# 12_Supply.net
KiCad netlist of a schematic drawn in Altium Designer
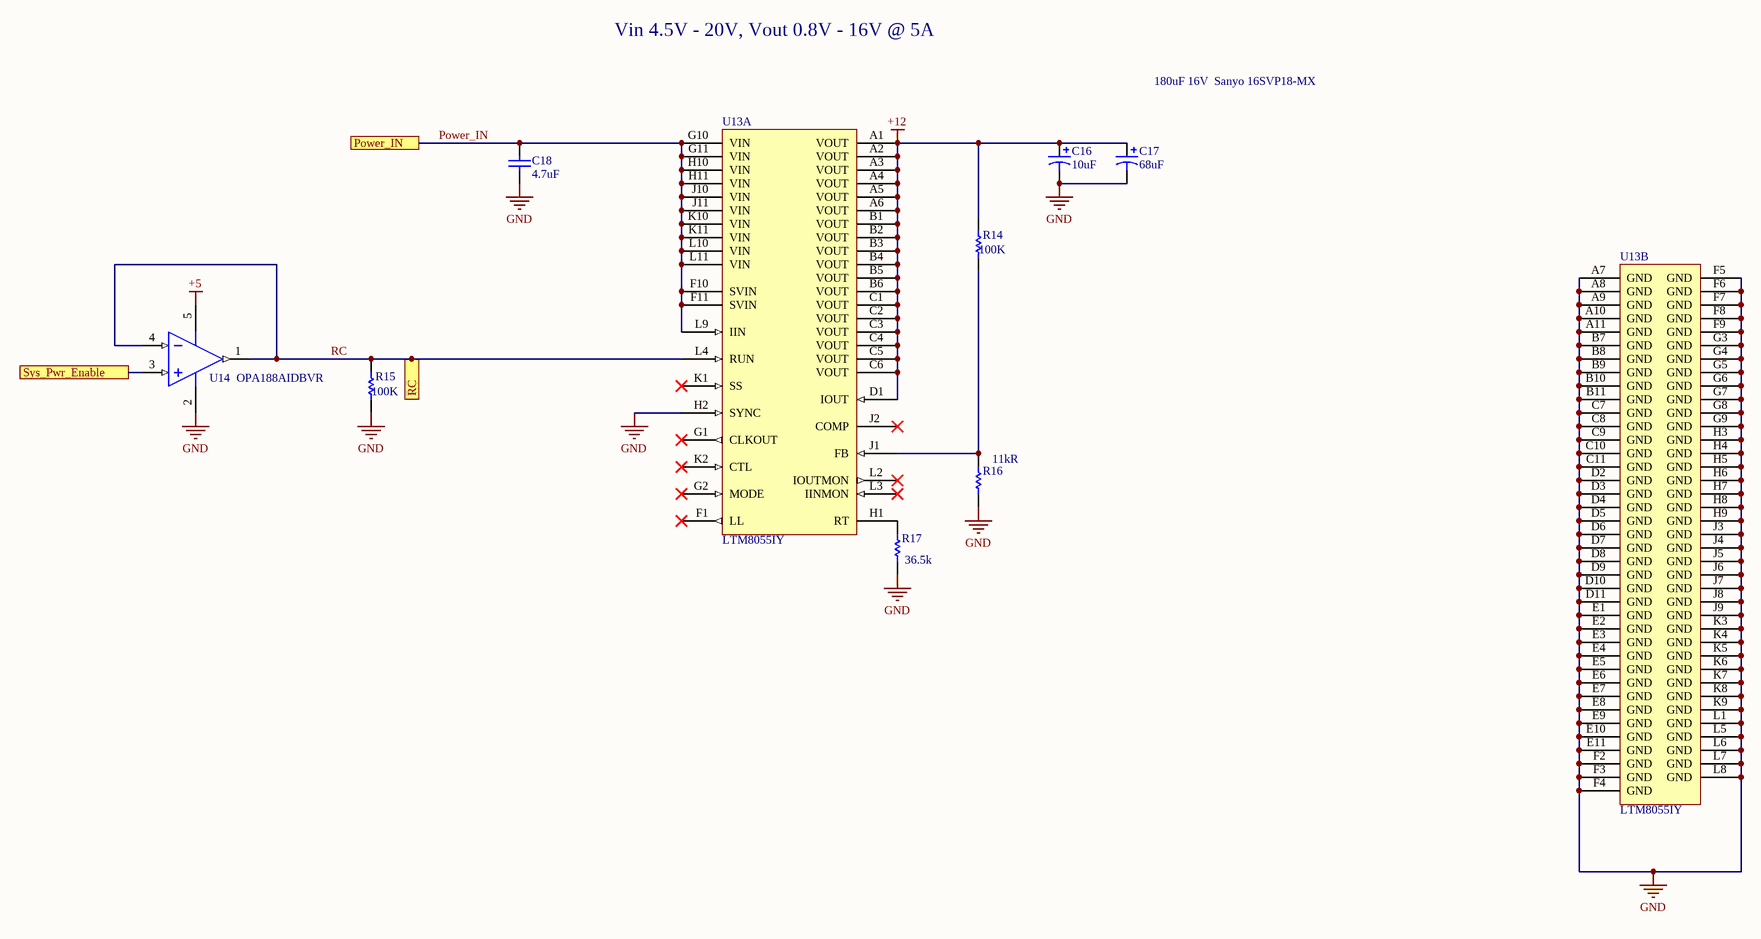
[diagram p0: 12_Supply.SchDoc]

(export (version "E")
  (design (tool "Eeschema 10.0.6"))
  (components
    (comp (ref "C16")
      (value "10uF")
      (footprint "C0805")
      (description "Polarized Capacitor (Surface Mount)")
      (libsource (lib "Miscellaneous Devices") (part "Cap Pol3"))
    )
    (comp (ref "C17")
      (value "68uF")
      (footprint "AVX-CAPC7343_V")
      (description "CAP TANT POLY 68UF 25V 2917")
      (fields
        (field (name "MANUFACTURER") "Kyocera AVX")
        (field (name "MANUFACTURER PART NUMBER") "TCJE686M025R0050")
      )
      (libsource (lib "Altium Content Vault") (part "AVX-CAP-P-2"))
    )
    (comp (ref "C18")
      (value "4.7uF")
      (footprint "CAPC1210(3225)100_M")
      (description "CAP CER 4.7UF 50V X7R 1210")
      (fields
        (field (name "MANUFACTURER") "Murata")
        (field (name "MANUFACTURER PART NUMBER") "GCM32ER71H475KA55K")
      )
      (libsource (lib "Altium Content Vault") (part "CAP"))
    )
    (comp (ref "R14")
      (value "RES SMD 100K OHM 1% 1/8W 0805")
      (footprint "RESC0805(2012)_M")
      (fields
        (field (name "MANUFACTURER") "Vishay")
        (field (name "MANUFACTURER PART NUMBER") "CRCW0805100KFKEA")
        (field (name "TOLERANCE") "1%")
        (field (name "RESISTANCE") "100K")
      )
      (libsource (lib "Altium Content Vault") (part "CMP-1013-00017-1"))
    )
    (comp (ref "R15")
      (value "RES SMD 100K OHM 1% 1/8W 0805")
      (footprint "RESC0805(2012)_M")
      (fields
        (field (name "MANUFACTURER") "Vishay")
        (field (name "MANUFACTURER PART NUMBER") "CRCW0805100KFKEA")
        (field (name "TOLERANCE") "1%")
        (field (name "RESISTANCE") "100K")
      )
      (libsource (lib "Altium Content Vault") (part "CMP-1013-00017-1"))
    )
    (comp (ref "R16")
      (value "RES SMD 11K OHM 1% 1/8W 0805")
      (footprint "RESC0805(2012)_M")
      (fields
        (field (name "MANUFACTURER") "TE Connectivity Holsworthy")
        (field (name "MANUFACTURER PART NUMBER") "CRG0805F11K")
        (field (name "RESISTANCE") "11kR")
        (field (name "TOLERANCE") "1%")
      )
      (libsource (lib "Altium Content Vault") (part "CMP-1013-00017-1"))
    )
    (comp (ref "R17")
      (value "RES SMD 35K OHM 1% 1/8W 0805")
      (footprint "RESC0805(2012)_M")
      (fields
        (field (name "MANUFACTURER") "Vishay")
        (field (name "MANUFACTURER PART NUMBER") "CRCW080536K5FKEA")
        (field (name "TOLERANCE") "1%")
        (field (name "RESISTANCE") "36.5k")
      )
      (libsource (lib "Altium Content Vault") (part "CMP-1013-00017-1"))
    )
    (comp (ref "U13")
      (value "LTM8055IY")
      (footprint "LT-BGA-121-15000X15000X4920")
      (description "Buck-Boost uModule Regulator, 8.5 A, 5 to 36 V, -40 to 125 degC, 121-Ball BGA, RoHS, Tray")
      (fields (field (name "MANUFACTURER") "LinearTechnology"))
      (libsource (lib "Altium Content Vault") (part "LT-LTM8055-BGA-121"))
    )
    (comp (ref "U14")
      (value "OPA188AIDBVR")
      (footprint "DBV0005A_M")
      (fields (field (name "MANUFACTURER") "Texas Instruments"))
      (libsource (lib "Altium Content Vault") (part "CMP-0809-00005-2"))
    )
  )
  (nets
    (net (code "1") (name "+5") (class "Default")
      (node (ref "U14") (pin "5") (pinfunction "V+_5") (pintype "power_in"))
    )
    (net (code "2") (name "+12") (class "Default")
      (node (ref "C16") (pin "1") (pinfunction "1_1") (pintype "passive"))
      (node (ref "C17") (pin "1") (pinfunction "1_1") (pintype "passive"))
      (node (ref "R14") (pin "1") (pinfunction "1_1") (pintype "passive"))
      (node (ref "U13") (pin "A1") (pinfunction "VOUT_A1") (pintype "power_in"))
      (node (ref "U13") (pin "A2") (pinfunction "VOUT_A2") (pintype "power_in"))
      (node (ref "U13") (pin "A3") (pinfunction "VOUT_A3") (pintype "power_in"))
      (node (ref "U13") (pin "A4") (pinfunction "VOUT_A4") (pintype "power_in"))
      (node (ref "U13") (pin "A5") (pinfunction "VOUT_A5") (pintype "power_in"))
      (node (ref "U13") (pin "A6") (pinfunction "VOUT_A6") (pintype "power_in"))
      (node (ref "U13") (pin "B1") (pinfunction "VOUT_B1") (pintype "power_in"))
      (node (ref "U13") (pin "B2") (pinfunction "VOUT_B2") (pintype "power_in"))
      (node (ref "U13") (pin "B3") (pinfunction "VOUT_B3") (pintype "power_in"))
      (node (ref "U13") (pin "B4") (pinfunction "VOUT_B4") (pintype "power_in"))
      (node (ref "U13") (pin "B5") (pinfunction "VOUT_B5") (pintype "power_in"))
      (node (ref "U13") (pin "B6") (pinfunction "VOUT_B6") (pintype "power_in"))
      (node (ref "U13") (pin "C1") (pinfunction "VOUT_C1") (pintype "power_in"))
      (node (ref "U13") (pin "C2") (pinfunction "VOUT_C2") (pintype "power_in"))
      (node (ref "U13") (pin "C3") (pinfunction "VOUT_C3") (pintype "power_in"))
      (node (ref "U13") (pin "C4") (pinfunction "VOUT_C4") (pintype "power_in"))
      (node (ref "U13") (pin "C5") (pinfunction "VOUT_C5") (pintype "power_in"))
      (node (ref "U13") (pin "C6") (pinfunction "VOUT_C6") (pintype "power_in"))
      (node (ref "U13") (pin "D1") (pinfunction "IOUT_D1") (pintype "input"))
    )
    (net (code "3") (name "/Power_IN") (class "Default")
      (node (ref "C18") (pin "2") (pinfunction "2_2") (pintype "passive"))
      (node (ref "U13") (pin "F10") (pinfunction "SVIN_F10") (pintype "power_in"))
      (node (ref "U13") (pin "F11") (pinfunction "SVIN_F11") (pintype "power_in"))
      (node (ref "U13") (pin "G10") (pinfunction "VIN_G10") (pintype "power_in"))
      (node (ref "U13") (pin "G11") (pinfunction "VIN_G11") (pintype "power_in"))
      (node (ref "U13") (pin "H10") (pinfunction "VIN_H10") (pintype "power_in"))
      (node (ref "U13") (pin "H11") (pinfunction "VIN_H11") (pintype "power_in"))
      (node (ref "U13") (pin "J10") (pinfunction "VIN_J10") (pintype "power_in"))
      (node (ref "U13") (pin "J11") (pinfunction "VIN_J11") (pintype "power_in"))
      (node (ref "U13") (pin "K10") (pinfunction "VIN_K10") (pintype "power_in"))
      (node (ref "U13") (pin "K11") (pinfunction "VIN_K11") (pintype "power_in"))
      (node (ref "U13") (pin "L10") (pinfunction "VIN_L10") (pintype "power_in"))
      (node (ref "U13") (pin "L11") (pinfunction "VIN_L11") (pintype "power_in"))
      (node (ref "U13") (pin "L9") (pinfunction "IIN_L9") (pintype "input"))
    )
    (net (code "4") (name "/RC") (class "Default")
      (node (ref "R15") (pin "1") (pinfunction "1_1") (pintype "passive"))
      (node (ref "U13") (pin "L4") (pinfunction "RUN_L4") (pintype "input"))
      (node (ref "U14") (pin "1") (pinfunction "OUT_1") (pintype "output"))
      (node (ref "U14") (pin "4") (pinfunction "IN-_4") (pintype "input"))
    )
    (net (code "5") (name "/Sys_Pwr_Enable") (class "Default")
      (node (ref "U14") (pin "3") (pinfunction "IN+_3") (pintype "input"))
    )
    (net (code "6") (name "GND") (class "Default")
      (node (ref "C16") (pin "2") (pinfunction "2_2") (pintype "passive"))
      (node (ref "C17") (pin "2") (pinfunction "2_2") (pintype "passive"))
      (node (ref "C18") (pin "1") (pinfunction "1_1") (pintype "passive"))
      (node (ref "R15") (pin "2") (pinfunction "2_2") (pintype "passive"))
      (node (ref "R16") (pin "2") (pinfunction "2_2") (pintype "passive"))
      (node (ref "R17") (pin "2") (pinfunction "2_2") (pintype "passive"))
      (node (ref "U13") (pin "A10") (pinfunction "GND_A10") (pintype "power_in"))
      (node (ref "U13") (pin "A11") (pinfunction "GND_A11") (pintype "power_in"))
      (node (ref "U13") (pin "A7") (pinfunction "GND_A7") (pintype "power_in"))
      (node (ref "U13") (pin "A8") (pinfunction "GND_A8") (pintype "power_in"))
      (node (ref "U13") (pin "A9") (pinfunction "GND_A9") (pintype "power_in"))
      (node (ref "U13") (pin "B10") (pinfunction "GND_B10") (pintype "power_in"))
      (node (ref "U13") (pin "B11") (pinfunction "GND_B11") (pintype "power_in"))
      (node (ref "U13") (pin "B7") (pinfunction "GND_B7") (pintype "power_in"))
      (node (ref "U13") (pin "B8") (pinfunction "GND_B8") (pintype "power_in"))
      (node (ref "U13") (pin "B9") (pinfunction "GND_B9") (pintype "power_in"))
      (node (ref "U13") (pin "C10") (pinfunction "GND_C10") (pintype "power_in"))
      (node (ref "U13") (pin "C11") (pinfunction "GND_C11") (pintype "power_in"))
      (node (ref "U13") (pin "C7") (pinfunction "GND_C7") (pintype "power_in"))
      (node (ref "U13") (pin "C8") (pinfunction "GND_C8") (pintype "power_in"))
      (node (ref "U13") (pin "C9") (pinfunction "GND_C9") (pintype "power_in"))
      (node (ref "U13") (pin "D10") (pinfunction "GND_D10") (pintype "power_in"))
      (node (ref "U13") (pin "D11") (pinfunction "GND_D11") (pintype "power_in"))
      (node (ref "U13") (pin "D2") (pinfunction "GND_D2") (pintype "power_in"))
      (node (ref "U13") (pin "D3") (pinfunction "GND_D3") (pintype "power_in"))
      (node (ref "U13") (pin "D4") (pinfunction "GND_D4") (pintype "power_in"))
      (node (ref "U13") (pin "D5") (pinfunction "GND_D5") (pintype "power_in"))
      (node (ref "U13") (pin "D6") (pinfunction "GND_D6") (pintype "power_in"))
      (node (ref "U13") (pin "D7") (pinfunction "GND_D7") (pintype "power_in"))
      (node (ref "U13") (pin "D8") (pinfunction "GND_D8") (pintype "power_in"))
      (node (ref "U13") (pin "D9") (pinfunction "GND_D9") (pintype "power_in"))
      (node (ref "U13") (pin "E1") (pinfunction "GND_E1") (pintype "power_in"))
      (node (ref "U13") (pin "E10") (pinfunction "GND_E10") (pintype "power_in"))
      (node (ref "U13") (pin "E11") (pinfunction "GND_E11") (pintype "power_in"))
      (node (ref "U13") (pin "E2") (pinfunction "GND_E2") (pintype "power_in"))
      (node (ref "U13") (pin "E3") (pinfunction "GND_E3") (pintype "power_in"))
      (node (ref "U13") (pin "E4") (pinfunction "GND_E4") (pintype "power_in"))
      (node (ref "U13") (pin "E5") (pinfunction "GND_E5") (pintype "power_in"))
      (node (ref "U13") (pin "E6") (pinfunction "GND_E6") (pintype "power_in"))
      (node (ref "U13") (pin "E7") (pinfunction "GND_E7") (pintype "power_in"))
      (node (ref "U13") (pin "E8") (pinfunction "GND_E8") (pintype "power_in"))
      (node (ref "U13") (pin "E9") (pinfunction "GND_E9") (pintype "power_in"))
      (node (ref "U13") (pin "F2") (pinfunction "GND_F2") (pintype "power_in"))
      (node (ref "U13") (pin "F3") (pinfunction "GND_F3") (pintype "power_in"))
      (node (ref "U13") (pin "F4") (pinfunction "GND_F4") (pintype "power_in"))
      (node (ref "U13") (pin "F5") (pinfunction "GND_F5") (pintype "power_in"))
      (node (ref "U13") (pin "F6") (pinfunction "GND_F6") (pintype "power_in"))
      (node (ref "U13") (pin "F7") (pinfunction "GND_F7") (pintype "power_in"))
      (node (ref "U13") (pin "F8") (pinfunction "GND_F8") (pintype "power_in"))
      (node (ref "U13") (pin "F9") (pinfunction "GND_F9") (pintype "power_in"))
      (node (ref "U13") (pin "G3") (pinfunction "GND_G3") (pintype "power_in"))
      (node (ref "U13") (pin "G4") (pinfunction "GND_G4") (pintype "power_in"))
      (node (ref "U13") (pin "G5") (pinfunction "GND_G5") (pintype "power_in"))
      (node (ref "U13") (pin "G6") (pinfunction "GND_G6") (pintype "power_in"))
      (node (ref "U13") (pin "G7") (pinfunction "GND_G7") (pintype "power_in"))
      (node (ref "U13") (pin "G8") (pinfunction "GND_G8") (pintype "power_in"))
      (node (ref "U13") (pin "G9") (pinfunction "GND_G9") (pintype "power_in"))
      (node (ref "U13") (pin "H2") (pinfunction "SYNC_H2") (pintype "input"))
      (node (ref "U13") (pin "H3") (pinfunction "GND_H3") (pintype "power_in"))
      (node (ref "U13") (pin "H4") (pinfunction "GND_H4") (pintype "power_in"))
      (node (ref "U13") (pin "H5") (pinfunction "GND_H5") (pintype "power_in"))
      (node (ref "U13") (pin "H6") (pinfunction "GND_H6") (pintype "power_in"))
      (node (ref "U13") (pin "H7") (pinfunction "GND_H7") (pintype "power_in"))
      (node (ref "U13") (pin "H8") (pinfunction "GND_H8") (pintype "power_in"))
      (node (ref "U13") (pin "H9") (pinfunction "GND_H9") (pintype "power_in"))
      (node (ref "U13") (pin "J3") (pinfunction "GND_J3") (pintype "power_in"))
      (node (ref "U13") (pin "J4") (pinfunction "GND_J4") (pintype "power_in"))
      (node (ref "U13") (pin "J5") (pinfunction "GND_J5") (pintype "power_in"))
      (node (ref "U13") (pin "J6") (pinfunction "GND_J6") (pintype "power_in"))
      (node (ref "U13") (pin "J7") (pinfunction "GND_J7") (pintype "power_in"))
      (node (ref "U13") (pin "J8") (pinfunction "GND_J8") (pintype "power_in"))
      (node (ref "U13") (pin "J9") (pinfunction "GND_J9") (pintype "power_in"))
      (node (ref "U13") (pin "K3") (pinfunction "GND_K3") (pintype "power_in"))
      (node (ref "U13") (pin "K4") (pinfunction "GND_K4") (pintype "power_in"))
      (node (ref "U13") (pin "K5") (pinfunction "GND_K5") (pintype "power_in"))
      (node (ref "U13") (pin "K6") (pinfunction "GND_K6") (pintype "power_in"))
      (node (ref "U13") (pin "K7") (pinfunction "GND_K7") (pintype "power_in"))
      (node (ref "U13") (pin "K8") (pinfunction "GND_K8") (pintype "power_in"))
      (node (ref "U13") (pin "K9") (pinfunction "GND_K9") (pintype "power_in"))
      (node (ref "U13") (pin "L1") (pinfunction "GND_L1") (pintype "power_in"))
      (node (ref "U13") (pin "L5") (pinfunction "GND_L5") (pintype "power_in"))
      (node (ref "U13") (pin "L6") (pinfunction "GND_L6") (pintype "power_in"))
      (node (ref "U13") (pin "L7") (pinfunction "GND_L7") (pintype "power_in"))
      (node (ref "U13") (pin "L8") (pinfunction "GND_L8") (pintype "power_in"))
      (node (ref "U14") (pin "2") (pinfunction "V-_2") (pintype "power_in"))
    )
    (net (code "7") (name "Net-(U13A-FB)") (class "Default")
      (node (ref "R14") (pin "2") (pinfunction "2_2") (pintype "passive"))
      (node (ref "R16") (pin "1") (pinfunction "1_1") (pintype "passive"))
      (node (ref "U13") (pin "J1") (pinfunction "FB_J1") (pintype "input"))
    )
    (net (code "8") (name "Net-(U13A-RT)") (class "Default")
      (node (ref "R17") (pin "1") (pinfunction "1_1") (pintype "passive"))
      (node (ref "U13") (pin "H1") (pinfunction "RT_H1") (pintype "passive"))
    )
    (net (code "9") (name "unconnected-(U13A-CLKOUT-PadG1)") (class "Default")
      (node (ref "U13") (pin "G1") (pinfunction "CLKOUT_G1") (pintype "output+no_connect"))
    )
    (net (code "10") (name "unconnected-(U13A-COMP-PadJ2)") (class "Default")
      (node (ref "U13") (pin "J2") (pinfunction "COMP_J2") (pintype "passive+no_connect"))
    )
    (net (code "11") (name "unconnected-(U13A-CTL-PadK2)") (class "Default")
      (node (ref "U13") (pin "K2") (pinfunction "CTL_K2") (pintype "input+no_connect"))
    )
    (net (code "12") (name "unconnected-(U13A-IINMON-PadL3)") (class "Default")
      (node (ref "U13") (pin "L3") (pinfunction "IINMON_L3") (pintype "input+no_connect"))
    )
    (net (code "13") (name "unconnected-(U13A-IOUTMON-PadL2)") (class "Default")
      (node (ref "U13") (pin "L2") (pinfunction "IOUTMON_L2") (pintype "output+no_connect"))
    )
    (net (code "14") (name "unconnected-(U13A-LL-PadF1)") (class "Default")
      (node (ref "U13") (pin "F1") (pinfunction "LL_F1") (pintype "output+no_connect"))
    )
    (net (code "15") (name "unconnected-(U13A-MODE-PadG2)") (class "Default")
      (node (ref "U13") (pin "G2") (pinfunction "MODE_G2") (pintype "input+no_connect"))
    )
    (net (code "16") (name "unconnected-(U13A-SS-PadK1)") (class "Default")
      (node (ref "U13") (pin "K1") (pinfunction "SS_K1") (pintype "input+no_connect"))
    )
  )
)
